# modul.net
KiCad netlist of a schematic drawn in EAGLE
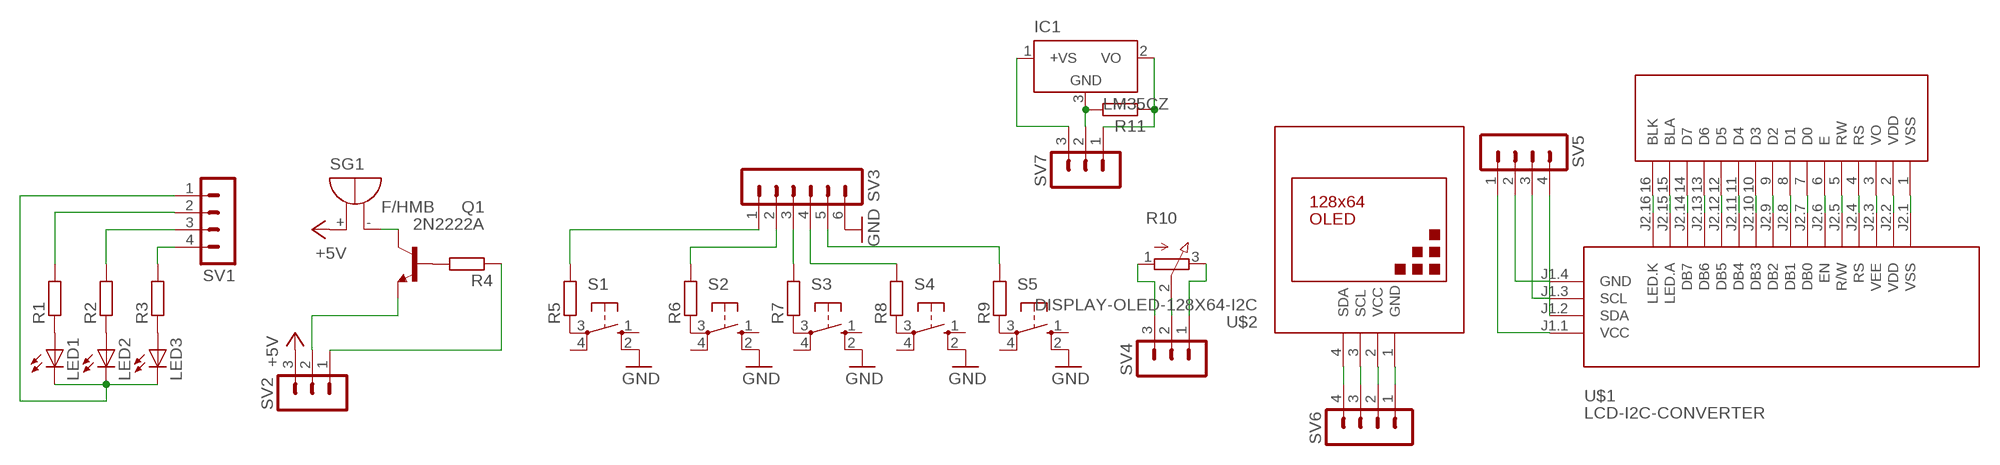
[diagram p0: schematic, sheet 1]

(export (version "E")
  (design (tool "Eeschema 10.0.6"))
  (components
    (comp (ref "IC1")
      (value "LM35CZ")
      (footprint "eagle-import:TO92")
      (libsource (lib "eagle-import") (part "LM35CZ"))
    )
    (comp (ref "LED1")
      (value "LED10MM")
      (footprint "eagle-import:LED10MM")
      (libsource (lib "eagle-import") (part "LED10MM"))
    )
    (comp (ref "LED2")
      (value "LED10MM")
      (footprint "eagle-import:LED10MM")
      (libsource (lib "eagle-import") (part "LED10MM"))
    )
    (comp (ref "LED3")
      (value "LED10MM")
      (footprint "eagle-import:LED10MM")
      (libsource (lib "eagle-import") (part "LED10MM"))
    )
    (comp (ref "Q1")
      (value "2N2222A")
      (footprint "eagle-import:TO18")
      (libsource (lib "eagle-import") (part "2N2222A"))
    )
    (comp (ref "R1")
      (value "R-EU_0204/5")
      (footprint "eagle-import:0204_5")
      (libsource (lib "eagle-import") (part "R-EU_0204/5"))
    )
    (comp (ref "R2")
      (value "R-EU_0204/5")
      (footprint "eagle-import:0204_5")
      (libsource (lib "eagle-import") (part "R-EU_0204/5"))
    )
    (comp (ref "R3")
      (value "R-EU_0204/5")
      (footprint "eagle-import:0204_5")
      (libsource (lib "eagle-import") (part "R-EU_0204/5"))
    )
    (comp (ref "R4")
      (value "R-EU_0204/5")
      (footprint "eagle-import:0204_5")
      (libsource (lib "eagle-import") (part "R-EU_0204/5"))
    )
    (comp (ref "R5")
      (value "R-EU_0204/5")
      (footprint "eagle-import:0204_5")
      (libsource (lib "eagle-import") (part "R-EU_0204/5"))
    )
    (comp (ref "R6")
      (value "R-EU_0204/5")
      (footprint "eagle-import:0204_5")
      (libsource (lib "eagle-import") (part "R-EU_0204/5"))
    )
    (comp (ref "R7")
      (value "R-EU_0204/5")
      (footprint "eagle-import:0204_5")
      (libsource (lib "eagle-import") (part "R-EU_0204/5"))
    )
    (comp (ref "R8")
      (value "R-EU_0204/5")
      (footprint "eagle-import:0204_5")
      (libsource (lib "eagle-import") (part "R-EU_0204/5"))
    )
    (comp (ref "R9")
      (value "R-EU_0204/5")
      (footprint "eagle-import:0204_5")
      (libsource (lib "eagle-import") (part "R-EU_0204/5"))
    )
    (comp (ref "R10")
      (value "3RP/1610N")
      (footprint "eagle-import:3RP_1610N")
      (libsource (lib "eagle-import") (part "3RP/1610N"))
    )
    (comp (ref "R11")
      (value "R-EU_0204/5")
      (footprint "eagle-import:0204_5")
      (libsource (lib "eagle-import") (part "R-EU_0204/5"))
    )
    (comp (ref "S1")
      (value "10-XX")
      (footprint "eagle-import:B3F-10XX")
      (fields (field (name "MPN") "B3F-1000"))
      (libsource (lib "eagle-import") (part "10-XX"))
    )
    (comp (ref "S2")
      (value "10-XX")
      (footprint "eagle-import:B3F-10XX")
      (fields (field (name "MPN") "B3F-1000"))
      (libsource (lib "eagle-import") (part "10-XX"))
    )
    (comp (ref "S3")
      (value "10-XX")
      (footprint "eagle-import:B3F-10XX")
      (fields (field (name "MPN") "B3F-1000"))
      (libsource (lib "eagle-import") (part "10-XX"))
    )
    (comp (ref "S4")
      (value "10-XX")
      (footprint "eagle-import:B3F-10XX")
      (fields (field (name "MPN") "B3F-1000"))
      (libsource (lib "eagle-import") (part "10-XX"))
    )
    (comp (ref "S5")
      (value "10-XX")
      (footprint "eagle-import:B3F-10XX")
      (fields (field (name "MPN") "B3F-1000"))
      (libsource (lib "eagle-import") (part "10-XX"))
    )
    (comp (ref "SG1")
      (value "F/HMB")
      (footprint "eagle-import:F_HMB")
      (libsource (lib "eagle-import") (part "F/HMB"))
    )
    (comp (ref "SV1")
      (value "MA04-1")
      (footprint "eagle-import:MA04-1")
      (libsource (lib "eagle-import") (part "MA04-1"))
    )
    (comp (ref "SV2")
      (value "MA03-1")
      (footprint "eagle-import:MA03-1")
      (libsource (lib "eagle-import") (part "MA03-1"))
    )
    (comp (ref "SV3")
      (value "MA06-1")
      (footprint "eagle-import:MA06-1")
      (libsource (lib "eagle-import") (part "MA06-1"))
    )
    (comp (ref "SV4")
      (value "MA03-1")
      (footprint "eagle-import:MA03-1")
      (libsource (lib "eagle-import") (part "MA03-1"))
    )
    (comp (ref "SV5")
      (value "MA04-1")
      (footprint "eagle-import:MA04-1")
      (libsource (lib "eagle-import") (part "MA04-1"))
    )
    (comp (ref "SV6")
      (value "MA04-1")
      (footprint "eagle-import:MA04-1")
      (libsource (lib "eagle-import") (part "MA04-1"))
    )
    (comp (ref "SV7")
      (value "MA03-1")
      (footprint "eagle-import:MA03-1")
      (libsource (lib "eagle-import") (part "MA03-1"))
    )
    (comp (ref "U$1")
      (value "LCD-I2C-CONVERTER")
      (footprint "eagle-import:LCD-I2C-CONVERTER")
      (libsource (lib "eagle-import") (part "LCD-I2C-CONVERTER"))
    )
    (comp (ref "U$2")
      (value "DISPLAY-OLED-128X64-I2C")
      (footprint "eagle-import:DISPLAY-OLED-128X64-I2C")
      (libsource (lib "eagle-import") (part "DISPLAY-OLED-128X64-I2C"))
    )
    (comp (ref "U$3")
      (value "2X16LCDTOP")
      (footprint "eagle-import:2X16LCDTOP")
      (libsource (lib "eagle-import") (part "2X16LCDTOP"))
    )
  )
  (nets
    (net (code "1") (name "+5V") (class "Default")
      (node (ref "SG1") (pin "+") (pinfunction "+_+") (pintype "passive"))
      (node (ref "SV2") (pin "3") (pinfunction "3_3") (pintype "passive"))
    )
    (net (code "2") (name "GND") (class "Default")
      (node (ref "S1") (pin "2") (pinfunction "S1_2") (pintype "passive"))
      (node (ref "S2") (pin "2") (pinfunction "S1_2") (pintype "passive"))
      (node (ref "S3") (pin "2") (pinfunction "S1_2") (pintype "passive"))
      (node (ref "S4") (pin "2") (pinfunction "S1_2") (pintype "passive"))
      (node (ref "S5") (pin "2") (pinfunction "S1_2") (pintype "passive"))
      (node (ref "SV3") (pin "6") (pinfunction "6_6") (pintype "passive"))
    )
    (net (code "3") (name "Net-(IC1-+VS)") (class "Default")
      (node (ref "IC1") (pin "1") (pinfunction "+VS_1") (pintype "input"))
      (node (ref "SV7") (pin "3") (pinfunction "3_3") (pintype "passive"))
    )
    (net (code "4") (name "Net-(IC1-GND)") (class "Default")
      (node (ref "IC1") (pin "3") (pinfunction "GND_3") (pintype "power_in"))
      (node (ref "R11") (pin "2") (pinfunction "2_2") (pintype "passive"))
      (node (ref "SV7") (pin "2") (pinfunction "2_2") (pintype "passive"))
    )
    (net (code "5") (name "Net-(IC1-VO)") (class "Default")
      (node (ref "IC1") (pin "2") (pinfunction "VO_2") (pintype "input"))
      (node (ref "R11") (pin "1") (pinfunction "1_1") (pintype "passive"))
      (node (ref "SV7") (pin "1") (pinfunction "1_1") (pintype "passive"))
    )
    (net (code "6") (name "Net-(LED1-C)") (class "Default")
      (node (ref "LED1") (pin "K") (pinfunction "C_K") (pintype "passive"))
      (node (ref "LED2") (pin "K") (pinfunction "C_K") (pintype "passive"))
      (node (ref "LED3") (pin "K") (pinfunction "C_K") (pintype "passive"))
      (node (ref "SV1") (pin "1") (pinfunction "1_1") (pintype "passive"))
    )
    (net (code "7") (name "Net-(LED1-PadA)") (class "Default")
      (node (ref "LED1") (pin "A") (pinfunction "A_A") (pintype "passive"))
      (node (ref "R1") (pin "1") (pinfunction "1_1") (pintype "passive"))
    )
    (net (code "8") (name "Net-(LED2-PadA)") (class "Default")
      (node (ref "LED2") (pin "A") (pinfunction "A_A") (pintype "passive"))
      (node (ref "R2") (pin "1") (pinfunction "1_1") (pintype "passive"))
    )
    (net (code "9") (name "Net-(LED3-PadA)") (class "Default")
      (node (ref "LED3") (pin "A") (pinfunction "A_A") (pintype "passive"))
      (node (ref "R3") (pin "1") (pinfunction "1_1") (pintype "passive"))
    )
    (net (code "10") (name "Net-(Q1-B)") (class "Default")
      (node (ref "Q1") (pin "2") (pinfunction "B_2") (pintype "passive"))
      (node (ref "R4") (pin "2") (pinfunction "2_2") (pintype "passive"))
    )
    (net (code "11") (name "Net-(Q1-C)") (class "Default")
      (node (ref "Q1") (pin "3") (pinfunction "C_3") (pintype "passive"))
      (node (ref "SG1") (pin "-") (pinfunction "-_-") (pintype "passive"))
    )
    (net (code "12") (name "Net-(Q1-E)") (class "Default")
      (node (ref "Q1") (pin "1") (pinfunction "E_1") (pintype "passive"))
      (node (ref "SV2") (pin "2") (pinfunction "2_2") (pintype "passive"))
    )
    (net (code "13") (name "Net-(R1-Pad2)") (class "Default")
      (node (ref "R1") (pin "2") (pinfunction "2_2") (pintype "passive"))
      (node (ref "SV1") (pin "2") (pinfunction "2_2") (pintype "passive"))
    )
    (net (code "14") (name "Net-(R2-Pad2)") (class "Default")
      (node (ref "R2") (pin "2") (pinfunction "2_2") (pintype "passive"))
      (node (ref "SV1") (pin "3") (pinfunction "3_3") (pintype "passive"))
    )
    (net (code "15") (name "Net-(R3-Pad2)") (class "Default")
      (node (ref "R3") (pin "2") (pinfunction "2_2") (pintype "passive"))
      (node (ref "SV1") (pin "4") (pinfunction "4_4") (pintype "passive"))
    )
    (net (code "16") (name "Net-(R4-Pad1)") (class "Default")
      (node (ref "R4") (pin "1") (pinfunction "1_1") (pintype "passive"))
      (node (ref "SV2") (pin "1") (pinfunction "1_1") (pintype "passive"))
    )
    (net (code "17") (name "Net-(R5-Pad2)") (class "Default")
      (node (ref "R5") (pin "2") (pinfunction "2_2") (pintype "passive"))
      (node (ref "SV3") (pin "1") (pinfunction "1_1") (pintype "passive"))
    )
    (net (code "18") (name "Net-(R6-Pad2)") (class "Default")
      (node (ref "R6") (pin "2") (pinfunction "2_2") (pintype "passive"))
      (node (ref "SV3") (pin "2") (pinfunction "2_2") (pintype "passive"))
    )
    (net (code "19") (name "Net-(R7-Pad2)") (class "Default")
      (node (ref "R7") (pin "2") (pinfunction "2_2") (pintype "passive"))
      (node (ref "SV3") (pin "3") (pinfunction "3_3") (pintype "passive"))
    )
    (net (code "20") (name "Net-(R8-Pad2)") (class "Default")
      (node (ref "R8") (pin "2") (pinfunction "2_2") (pintype "passive"))
      (node (ref "SV3") (pin "4") (pinfunction "4_4") (pintype "passive"))
    )
    (net (code "21") (name "Net-(R9-Pad2)") (class "Default")
      (node (ref "R9") (pin "2") (pinfunction "2_2") (pintype "passive"))
      (node (ref "SV3") (pin "5") (pinfunction "5_5") (pintype "passive"))
    )
    (net (code "22") (name "Net-(R10-A)") (class "Default")
      (node (ref "R10") (pin "1") (pinfunction "A_1") (pintype "passive"))
      (node (ref "SV4") (pin "3") (pinfunction "3_3") (pintype "passive"))
    )
    (net (code "23") (name "Net-(R10-E)") (class "Default")
      (node (ref "R10") (pin "3") (pinfunction "E_3") (pintype "passive"))
      (node (ref "SV4") (pin "1") (pinfunction "1_1") (pintype "passive"))
    )
    (net (code "24") (name "Net-(R10-S)") (class "Default")
      (node (ref "R10") (pin "2") (pinfunction "S_2") (pintype "passive"))
      (node (ref "SV4") (pin "2") (pinfunction "2_2") (pintype "passive"))
    )
    (net (code "25") (name "Net-(S1-P)") (class "Default")
      (node (ref "R5") (pin "1") (pinfunction "1_1") (pintype "passive"))
      (node (ref "S1") (pin "3") (pinfunction "P_3") (pintype "passive"))
    )
    (net (code "26") (name "Net-(S2-P)") (class "Default")
      (node (ref "R6") (pin "1") (pinfunction "1_1") (pintype "passive"))
      (node (ref "S2") (pin "3") (pinfunction "P_3") (pintype "passive"))
    )
    (net (code "27") (name "Net-(S3-P)") (class "Default")
      (node (ref "R7") (pin "1") (pinfunction "1_1") (pintype "passive"))
      (node (ref "S3") (pin "3") (pinfunction "P_3") (pintype "passive"))
    )
    (net (code "28") (name "Net-(S4-P)") (class "Default")
      (node (ref "R8") (pin "1") (pinfunction "1_1") (pintype "passive"))
      (node (ref "S4") (pin "3") (pinfunction "P_3") (pintype "passive"))
    )
    (net (code "29") (name "Net-(S5-P)") (class "Default")
      (node (ref "R9") (pin "1") (pinfunction "1_1") (pintype "passive"))
      (node (ref "S5") (pin "3") (pinfunction "P_3") (pintype "passive"))
    )
    (net (code "30") (name "Net-(U$1-DB0)") (class "Default")
      (node (ref "U$1") (pin "J2.7") (pinfunction "DB0_J2.7") (pintype "bidirectional"))
      (node (ref "U$3") (pin "7") (pinfunction "D0_7") (pintype "bidirectional"))
    )
    (net (code "31") (name "Net-(U$1-DB1)") (class "Default")
      (node (ref "U$1") (pin "J2.8") (pinfunction "DB1_J2.8") (pintype "bidirectional"))
      (node (ref "U$3") (pin "8") (pinfunction "D1_8") (pintype "bidirectional"))
    )
    (net (code "32") (name "Net-(U$1-DB2)") (class "Default")
      (node (ref "U$1") (pin "J2.9") (pinfunction "DB2_J2.9") (pintype "bidirectional"))
      (node (ref "U$3") (pin "9") (pinfunction "D2_9") (pintype "bidirectional"))
    )
    (net (code "33") (name "Net-(U$1-DB3)") (class "Default")
      (node (ref "U$1") (pin "J2.10") (pinfunction "DB3_J2.10") (pintype "bidirectional"))
      (node (ref "U$3") (pin "10") (pinfunction "D3_10") (pintype "bidirectional"))
    )
    (net (code "34") (name "Net-(U$1-DB4)") (class "Default")
      (node (ref "U$1") (pin "J2.11") (pinfunction "DB4_J2.11") (pintype "bidirectional"))
      (node (ref "U$3") (pin "11") (pinfunction "D4_11") (pintype "bidirectional"))
    )
    (net (code "35") (name "Net-(U$1-DB5)") (class "Default")
      (node (ref "U$1") (pin "J2.12") (pinfunction "DB5_J2.12") (pintype "bidirectional"))
      (node (ref "U$3") (pin "12") (pinfunction "D5_12") (pintype "bidirectional"))
    )
    (net (code "36") (name "Net-(U$1-DB6)") (class "Default")
      (node (ref "U$1") (pin "J2.13") (pinfunction "DB6_J2.13") (pintype "bidirectional"))
      (node (ref "U$3") (pin "13") (pinfunction "D6_13") (pintype "bidirectional"))
    )
    (net (code "37") (name "Net-(U$1-DB7)") (class "Default")
      (node (ref "U$1") (pin "J2.14") (pinfunction "DB7_J2.14") (pintype "bidirectional"))
      (node (ref "U$3") (pin "14") (pinfunction "D7_14") (pintype "bidirectional"))
    )
    (net (code "38") (name "Net-(U$1-EN)") (class "Default")
      (node (ref "U$1") (pin "J2.6") (pinfunction "EN_J2.6") (pintype "bidirectional"))
      (node (ref "U$3") (pin "6") (pinfunction "E_6") (pintype "bidirectional"))
    )
    (net (code "39") (name "Net-(U$1-GND)") (class "Default")
      (node (ref "SV5") (pin "2") (pinfunction "2_2") (pintype "passive"))
      (node (ref "U$1") (pin "J1.4") (pinfunction "GND_J1.4") (pintype "power_in"))
    )
    (net (code "40") (name "Net-(U$1-LED.A)") (class "Default")
      (node (ref "U$1") (pin "J2.15") (pinfunction "LED.A_J2.15") (pintype "bidirectional"))
      (node (ref "U$3") (pin "15") (pinfunction "BLA_15") (pintype "bidirectional"))
    )
    (net (code "41") (name "Net-(U$1-LED.K)") (class "Default")
      (node (ref "U$1") (pin "J2.16") (pinfunction "LED.K_J2.16") (pintype "bidirectional"))
      (node (ref "U$3") (pin "16") (pinfunction "BLK_16") (pintype "bidirectional"))
    )
    (net (code "42") (name "Net-(U$1-RS)") (class "Default")
      (node (ref "U$1") (pin "J2.4") (pinfunction "RS_J2.4") (pintype "bidirectional"))
      (node (ref "U$3") (pin "4") (pinfunction "RS_4") (pintype "bidirectional"))
    )
    (net (code "43") (name "Net-(U$1-R{slash}W)") (class "Default")
      (node (ref "U$1") (pin "J2.5") (pinfunction "R/W_J2.5") (pintype "bidirectional"))
      (node (ref "U$3") (pin "5") (pinfunction "RW_5") (pintype "bidirectional"))
    )
    (net (code "44") (name "Net-(U$1-SCL)") (class "Default")
      (node (ref "SV5") (pin "3") (pinfunction "3_3") (pintype "passive"))
      (node (ref "U$1") (pin "J1.3") (pinfunction "SCL_J1.3") (pintype "bidirectional"))
    )
    (net (code "45") (name "Net-(U$1-SDA)") (class "Default")
      (node (ref "SV5") (pin "4") (pinfunction "4_4") (pintype "passive"))
      (node (ref "U$1") (pin "J1.2") (pinfunction "SDA_J1.2") (pintype "bidirectional"))
    )
    (net (code "46") (name "Net-(U$1-VCC)") (class "Default")
      (node (ref "SV5") (pin "1") (pinfunction "1_1") (pintype "passive"))
      (node (ref "U$1") (pin "J1.1") (pinfunction "VCC_J1.1") (pintype "power_in"))
    )
    (net (code "47") (name "Net-(U$1-VDD)") (class "Default")
      (node (ref "U$1") (pin "J2.2") (pinfunction "VDD_J2.2") (pintype "bidirectional"))
      (node (ref "U$3") (pin "2") (pinfunction "VDD_2") (pintype "bidirectional"))
    )
    (net (code "48") (name "Net-(U$1-VEE)") (class "Default")
      (node (ref "U$1") (pin "J2.3") (pinfunction "VEE_J2.3") (pintype "bidirectional"))
      (node (ref "U$3") (pin "3") (pinfunction "VO_3") (pintype "bidirectional"))
    )
    (net (code "49") (name "Net-(U$1-VSS)") (class "Default")
      (node (ref "U$1") (pin "J2.1") (pinfunction "VSS_J2.1") (pintype "bidirectional"))
      (node (ref "U$3") (pin "1") (pinfunction "VSS_1") (pintype "bidirectional"))
    )
    (net (code "50") (name "Net-(U$2-GND)") (class "Default")
      (node (ref "SV6") (pin "1") (pinfunction "1_1") (pintype "passive"))
      (node (ref "U$2") (pin "1") (pinfunction "GND_1") (pintype "power_in"))
    )
    (net (code "51") (name "Net-(U$2-SCL)") (class "Default")
      (node (ref "SV6") (pin "3") (pinfunction "3_3") (pintype "passive"))
      (node (ref "U$2") (pin "3") (pinfunction "SCL_3") (pintype "bidirectional"))
    )
    (net (code "52") (name "Net-(U$2-SDA)") (class "Default")
      (node (ref "SV6") (pin "4") (pinfunction "4_4") (pintype "passive"))
      (node (ref "U$2") (pin "4") (pinfunction "SDA_4") (pintype "bidirectional"))
    )
    (net (code "53") (name "Net-(U$2-VCC)") (class "Default")
      (node (ref "SV6") (pin "2") (pinfunction "2_2") (pintype "passive"))
      (node (ref "U$2") (pin "2") (pinfunction "VCC_2") (pintype "power_in"))
    )
    (net (code "54") (name "unconnected-(S1-P1-Pad4)") (class "Default")
      (node (ref "S1") (pin "4") (pinfunction "P1_4") (pintype "passive"))
    )
    (net (code "55") (name "unconnected-(S1-S-Pad1)") (class "Default")
      (node (ref "S1") (pin "1") (pinfunction "S_1") (pintype "passive"))
    )
    (net (code "56") (name "unconnected-(S2-P1-Pad4)") (class "Default")
      (node (ref "S2") (pin "4") (pinfunction "P1_4") (pintype "passive"))
    )
    (net (code "57") (name "unconnected-(S2-S-Pad1)") (class "Default")
      (node (ref "S2") (pin "1") (pinfunction "S_1") (pintype "passive"))
    )
    (net (code "58") (name "unconnected-(S3-P1-Pad4)") (class "Default")
      (node (ref "S3") (pin "4") (pinfunction "P1_4") (pintype "passive"))
    )
    (net (code "59") (name "unconnected-(S3-S-Pad1)") (class "Default")
      (node (ref "S3") (pin "1") (pinfunction "S_1") (pintype "passive"))
    )
    (net (code "60") (name "unconnected-(S4-P1-Pad4)") (class "Default")
      (node (ref "S4") (pin "4") (pinfunction "P1_4") (pintype "passive"))
    )
    (net (code "61") (name "unconnected-(S4-S-Pad1)") (class "Default")
      (node (ref "S4") (pin "1") (pinfunction "S_1") (pintype "passive"))
    )
    (net (code "62") (name "unconnected-(S5-P1-Pad4)") (class "Default")
      (node (ref "S5") (pin "4") (pinfunction "P1_4") (pintype "passive"))
    )
    (net (code "63") (name "unconnected-(S5-S-Pad1)") (class "Default")
      (node (ref "S5") (pin "1") (pinfunction "S_1") (pintype "passive"))
    )
  )
)
